# PIIzza_TIme_updated.net
KiCad netlist of a schematic drawn in EAGLE
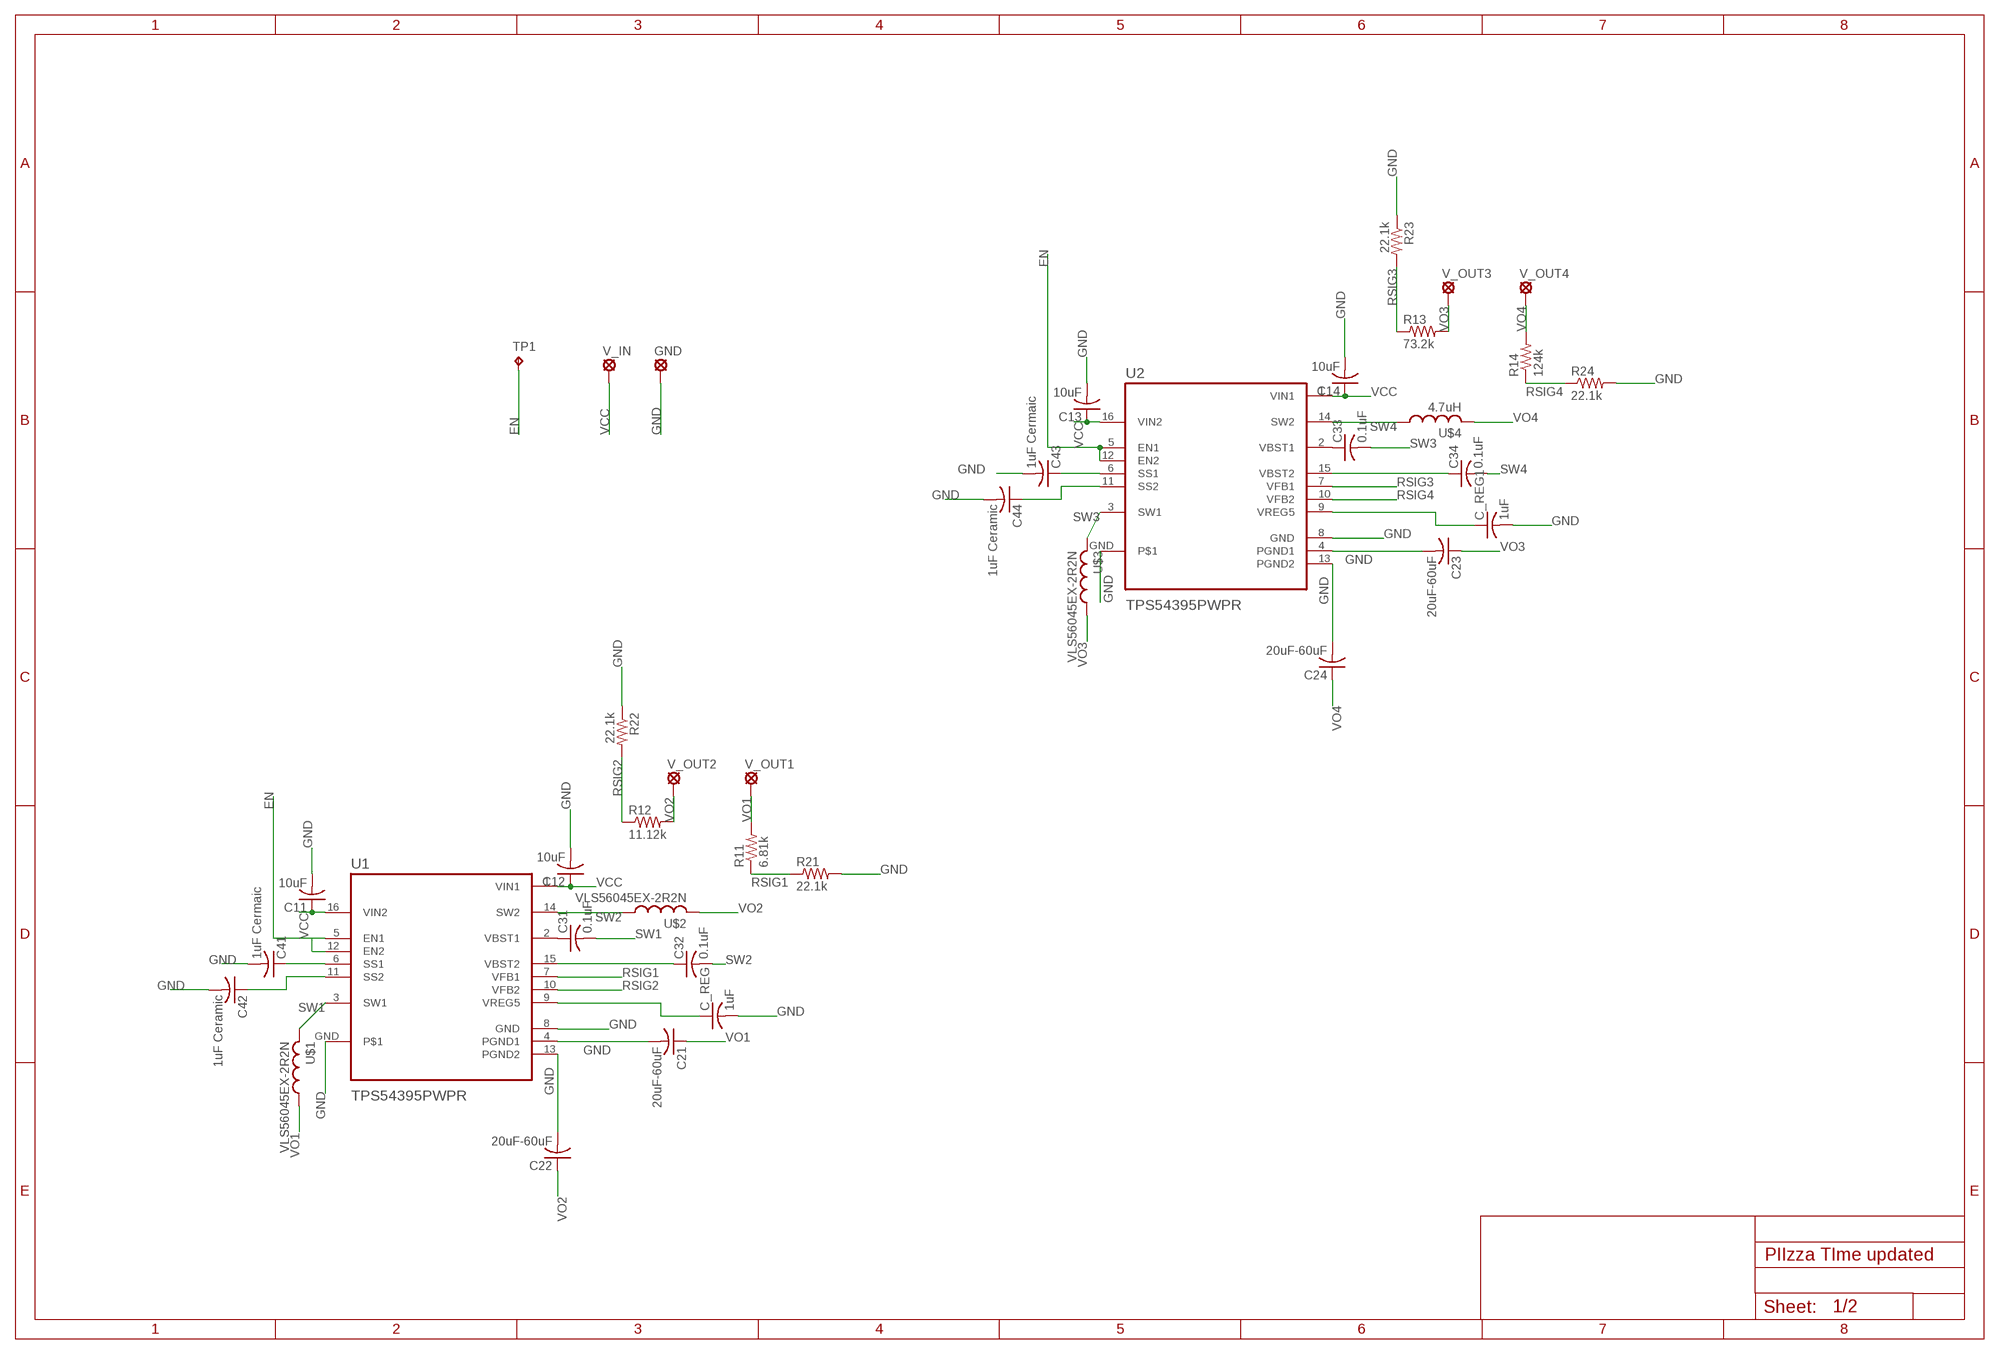
[diagram p0: schematic, sheet 1]
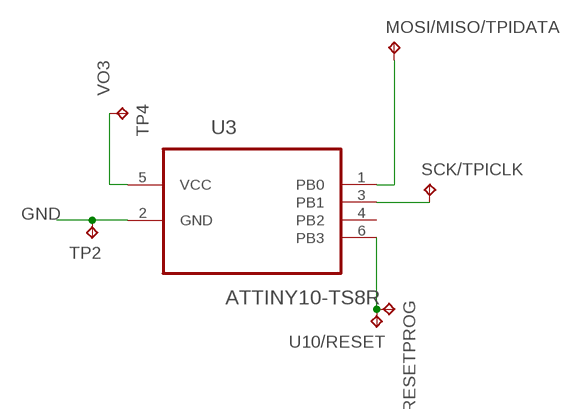
[diagram p1: schematic, sheet 2]

(export (version "E")
  (design (tool "Eeschema 10.0.6"))
  (components
    (comp (ref "MOSI/MISO/TPIDATA")
      (value "TPB2,54")
      (footprint "eagle-import:B2,54")
      (libsource (lib "eagle-import") (part "TPB2,54"))
    )
    (comp (ref "RESETPROG")
      (value "TPB2,54")
      (footprint "eagle-import:B2,54")
      (libsource (lib "eagle-import") (part "TPB2,54"))
    )
    (comp (ref "SCK/TPICLK")
      (value "TPB2,54")
      (footprint "eagle-import:B2,54")
      (libsource (lib "eagle-import") (part "TPB2,54"))
    )
    (comp (ref "TP2")
      (value "TPB2,54")
      (footprint "eagle-import:B2,54")
      (libsource (lib "eagle-import") (part "TPB2,54"))
    )
    (comp (ref "TP4")
      (value "TPB2,54")
      (footprint "eagle-import:B2,54")
      (libsource (lib "eagle-import") (part "TPB2,54"))
    )
    (comp (ref "U3")
      (value "ATTINY10-TS8R")
      (footprint "eagle-import:SOT95P280X145-6N")
      (fields (field (name "MF") "Microchip"))
      (libsource (lib "eagle-import") (part "ATTINY10-TS8R"))
    )
    (comp (ref "U10/RESET")
      (value "TPB2,54")
      (footprint "eagle-import:B2,54")
      (libsource (lib "eagle-import") (part "TPB2,54"))
    )
    (comp (ref "C11")
      (value "10uF")
      (footprint "eagle-import:C0805")
      (libsource (lib "eagle-import") (part "C-USC0805"))
    )
    (comp (ref "C12")
      (value "10uF")
      (footprint "eagle-import:C0805")
      (libsource (lib "eagle-import") (part "C-USC0805"))
    )
    (comp (ref "C13")
      (value "10uF")
      (footprint "eagle-import:C0805")
      (libsource (lib "eagle-import") (part "C-USC0805"))
    )
    (comp (ref "C14")
      (value "10uF")
      (footprint "eagle-import:C0805")
      (libsource (lib "eagle-import") (part "C-USC0805"))
    )
    (comp (ref "C21")
      (value "20uF-60uF")
      (footprint "eagle-import:C0805")
      (libsource (lib "eagle-import") (part "C-USC0805"))
    )
    (comp (ref "C22")
      (value "20uF-60uF")
      (footprint "eagle-import:C0805")
      (libsource (lib "eagle-import") (part "C-USC0805"))
    )
    (comp (ref "C23")
      (value "20uF-60uF")
      (footprint "eagle-import:C0805")
      (libsource (lib "eagle-import") (part "C-USC0805"))
    )
    (comp (ref "C24")
      (value "20uF-60uF")
      (footprint "eagle-import:C0805")
      (libsource (lib "eagle-import") (part "C-USC0805"))
    )
    (comp (ref "C31")
      (value "0.1uF")
      (footprint "eagle-import:C0805")
      (libsource (lib "eagle-import") (part "C-USC0805"))
    )
    (comp (ref "C32")
      (value "0.1uF")
      (footprint "eagle-import:C0805")
      (libsource (lib "eagle-import") (part "C-USC0805"))
    )
    (comp (ref "C33")
      (value "0.1uF")
      (footprint "eagle-import:C0805")
      (libsource (lib "eagle-import") (part "C-USC0805"))
    )
    (comp (ref "C34")
      (value "0.1uF")
      (footprint "eagle-import:C0805")
      (libsource (lib "eagle-import") (part "C-USC0805"))
    )
    (comp (ref "C41")
      (value "1uF Cermaic")
      (footprint "eagle-import:C0805")
      (libsource (lib "eagle-import") (part "C-USC0805"))
    )
    (comp (ref "C42")
      (value "1uF Ceramic")
      (footprint "eagle-import:C0805")
      (libsource (lib "eagle-import") (part "C-USC0805"))
    )
    (comp (ref "C43")
      (value "1uF Cermaic")
      (footprint "eagle-import:C0805")
      (libsource (lib "eagle-import") (part "C-USC0805"))
    )
    (comp (ref "C44")
      (value "1uF Ceramic")
      (footprint "eagle-import:C0805")
      (libsource (lib "eagle-import") (part "C-USC0805"))
    )
    (comp (ref "C_REG")
      (value "1uF")
      (footprint "eagle-import:C0805")
      (libsource (lib "eagle-import") (part "C-USC0805"))
    )
    (comp (ref "C_REG1")
      (value "1uF")
      (footprint "eagle-import:C0805")
      (libsource (lib "eagle-import") (part "C-USC0805"))
    )
    (comp (ref "GND")
      (value "SE11")
      (footprint "eagle-import:SE11")
      (libsource (lib "eagle-import") (part "SE11"))
    )
    (comp (ref "R11")
      (value "6.81k")
      (footprint "eagle-import:M0805")
      (libsource (lib "eagle-import") (part "R-US_M0805"))
    )
    (comp (ref "R12")
      (value "11.12k")
      (footprint "eagle-import:M0805")
      (libsource (lib "eagle-import") (part "R-US_M0805"))
    )
    (comp (ref "R13")
      (value "73.2k")
      (footprint "eagle-import:M0805")
      (libsource (lib "eagle-import") (part "R-US_M0805"))
    )
    (comp (ref "R14")
      (value "124k")
      (footprint "eagle-import:M0805")
      (libsource (lib "eagle-import") (part "R-US_M0805"))
    )
    (comp (ref "R21")
      (value "22.1k")
      (footprint "eagle-import:M0805")
      (libsource (lib "eagle-import") (part "R-US_M0805"))
    )
    (comp (ref "R22")
      (value "22.1k")
      (footprint "eagle-import:M0805")
      (libsource (lib "eagle-import") (part "R-US_M0805"))
    )
    (comp (ref "R23")
      (value "22.1k")
      (footprint "eagle-import:M0805")
      (libsource (lib "eagle-import") (part "R-US_M0805"))
    )
    (comp (ref "R24")
      (value "22.1k")
      (footprint "eagle-import:M0805")
      (libsource (lib "eagle-import") (part "R-US_M0805"))
    )
    (comp (ref "TP1")
      (value "TPB1,27")
      (footprint "eagle-import:B1,27")
      (libsource (lib "eagle-import") (part "TPB1,27"))
    )
    (comp (ref "U$1")
      (value "VLS56045EX-2R2N")
      (footprint "eagle-import:VLS")
      (libsource (lib "eagle-import") (part "VLS56045EX-2R2N"))
    )
    (comp (ref "U$2")
      (value "VLS56045EX-2R2N")
      (footprint "eagle-import:VLS")
      (libsource (lib "eagle-import") (part "VLS56045EX-2R2N"))
    )
    (comp (ref "U$3")
      (value "VLS56045EX-2R2N")
      (footprint "eagle-import:VLS")
      (libsource (lib "eagle-import") (part "VLS56045EX-2R2N"))
    )
    (comp (ref "U$4")
      (value "4.7uH")
      (footprint "eagle-import:VLS")
      (libsource (lib "eagle-import") (part "VLS56045EX-2R2N"))
    )
    (comp (ref "U1")
      (value "TPS54395PWPR")
      (footprint "eagle-import:SOP65P640X120-17N")
      (fields (field (name "MF") "Texas Instruments"))
      (libsource (lib "eagle-import") (part "TPS54395PWPR"))
    )
    (comp (ref "U2")
      (value "TPS54395PWPR")
      (footprint "eagle-import:SOP65P640X120-17N")
      (fields (field (name "MF") "Texas Instruments"))
      (libsource (lib "eagle-import") (part "TPS54395PWPR"))
    )
    (comp (ref "V_IN")
      (value "LSP11")
      (footprint "eagle-import:LSP11")
      (libsource (lib "eagle-import") (part "LSP11"))
    )
    (comp (ref "V_OUT1")
      (value "LSP11")
      (footprint "eagle-import:LSP11")
      (libsource (lib "eagle-import") (part "LSP11"))
    )
    (comp (ref "V_OUT2")
      (value "LSP11")
      (footprint "eagle-import:LSP11")
      (libsource (lib "eagle-import") (part "LSP11"))
    )
    (comp (ref "V_OUT3")
      (value "LSP11")
      (footprint "eagle-import:LSP11")
      (libsource (lib "eagle-import") (part "LSP11"))
    )
    (comp (ref "V_OUT4")
      (value "LSP11")
      (footprint "eagle-import:LSP11")
      (libsource (lib "eagle-import") (part "LSP11"))
    )
  )
  (nets
    (net (code "1") (name "EN") (class "Default")
      (node (ref "TP1") (pin "TP") (pinfunction "TP_TP") (pintype "input"))
      (node (ref "U1") (pin "12") (pinfunction "EN2_12") (pintype "bidirectional"))
      (node (ref "U1") (pin "5") (pinfunction "EN1_5") (pintype "bidirectional"))
      (node (ref "U2") (pin "12") (pinfunction "EN2_12") (pintype "bidirectional"))
      (node (ref "U2") (pin "5") (pinfunction "EN1_5") (pintype "bidirectional"))
    )
    (net (code "2") (name "GND") (class "Default")
      (node (ref "C11") (pin "2") (pinfunction "2_2") (pintype "passive"))
      (node (ref "C12") (pin "2") (pinfunction "2_2") (pintype "passive"))
      (node (ref "C13") (pin "2") (pinfunction "2_2") (pintype "passive"))
      (node (ref "C14") (pin "2") (pinfunction "2_2") (pintype "passive"))
      (node (ref "C21") (pin "2") (pinfunction "2_2") (pintype "passive"))
      (node (ref "C22") (pin "2") (pinfunction "2_2") (pintype "passive"))
      (node (ref "C23") (pin "2") (pinfunction "2_2") (pintype "passive"))
      (node (ref "C24") (pin "2") (pinfunction "2_2") (pintype "passive"))
      (node (ref "C41") (pin "2") (pinfunction "2_2") (pintype "passive"))
      (node (ref "C42") (pin "2") (pinfunction "2_2") (pintype "passive"))
      (node (ref "C43") (pin "2") (pinfunction "2_2") (pintype "passive"))
      (node (ref "C44") (pin "2") (pinfunction "2_2") (pintype "passive"))
      (node (ref "C_REG") (pin "2") (pinfunction "2_2") (pintype "passive"))
      (node (ref "C_REG1") (pin "2") (pinfunction "2_2") (pintype "passive"))
      (node (ref "GND") (pin "MP") (pinfunction "MP_MP") (pintype "passive"))
      (node (ref "R21") (pin "2") (pinfunction "2_2") (pintype "passive"))
      (node (ref "R22") (pin "1") (pinfunction "1_1") (pintype "passive"))
      (node (ref "R23") (pin "1") (pinfunction "1_1") (pintype "passive"))
      (node (ref "R24") (pin "2") (pinfunction "2_2") (pintype "passive"))
      (node (ref "TP2") (pin "TP") (pinfunction "TP_TP") (pintype "input"))
      (node (ref "U1") (pin "13") (pinfunction "PGND2_13") (pintype "power_in"))
      (node (ref "U1") (pin "4") (pinfunction "PGND1_4") (pintype "power_in"))
      (node (ref "U1") (pin "8") (pinfunction "GND_8") (pintype "power_in"))
      (node (ref "U1") (pin "GND") (pinfunction "P$1_GND") (pintype "bidirectional"))
      (node (ref "U2") (pin "13") (pinfunction "PGND2_13") (pintype "power_in"))
      (node (ref "U2") (pin "4") (pinfunction "PGND1_4") (pintype "power_in"))
      (node (ref "U2") (pin "8") (pinfunction "GND_8") (pintype "power_in"))
      (node (ref "U2") (pin "GND") (pinfunction "P$1_GND") (pintype "bidirectional"))
      (node (ref "U3") (pin "2") (pinfunction "GND_2") (pintype "passive"))
    )
    (net (code "3") (name "Net-(U1-SS1)") (class "Default")
      (node (ref "C41") (pin "1") (pinfunction "1_1") (pintype "passive"))
      (node (ref "U1") (pin "6") (pinfunction "SS1_6") (pintype "bidirectional"))
    )
    (net (code "4") (name "Net-(U1-SS2)") (class "Default")
      (node (ref "C42") (pin "1") (pinfunction "1_1") (pintype "passive"))
      (node (ref "U1") (pin "11") (pinfunction "SS2_11") (pintype "bidirectional"))
    )
    (net (code "5") (name "Net-(U1-VBST1)") (class "Default")
      (node (ref "C31") (pin "1") (pinfunction "1_1") (pintype "passive"))
      (node (ref "U1") (pin "2") (pinfunction "VBST1_2") (pintype "bidirectional"))
    )
    (net (code "6") (name "Net-(U1-VBST2)") (class "Default")
      (node (ref "C32") (pin "1") (pinfunction "1_1") (pintype "passive"))
      (node (ref "U1") (pin "15") (pinfunction "VBST2_15") (pintype "bidirectional"))
    )
    (net (code "7") (name "Net-(U1-VREG5)") (class "Default")
      (node (ref "C_REG") (pin "1") (pinfunction "1_1") (pintype "passive"))
      (node (ref "U1") (pin "9") (pinfunction "VREG5_9") (pintype "bidirectional"))
    )
    (net (code "8") (name "Net-(U2-SS1)") (class "Default")
      (node (ref "C43") (pin "1") (pinfunction "1_1") (pintype "passive"))
      (node (ref "U2") (pin "6") (pinfunction "SS1_6") (pintype "bidirectional"))
    )
    (net (code "9") (name "Net-(U2-SS2)") (class "Default")
      (node (ref "C44") (pin "1") (pinfunction "1_1") (pintype "passive"))
      (node (ref "U2") (pin "11") (pinfunction "SS2_11") (pintype "bidirectional"))
    )
    (net (code "10") (name "Net-(U2-VBST1)") (class "Default")
      (node (ref "C33") (pin "1") (pinfunction "1_1") (pintype "passive"))
      (node (ref "U2") (pin "2") (pinfunction "VBST1_2") (pintype "bidirectional"))
    )
    (net (code "11") (name "Net-(U2-VBST2)") (class "Default")
      (node (ref "C34") (pin "1") (pinfunction "1_1") (pintype "passive"))
      (node (ref "U2") (pin "15") (pinfunction "VBST2_15") (pintype "bidirectional"))
    )
    (net (code "12") (name "Net-(U2-VREG5)") (class "Default")
      (node (ref "C_REG1") (pin "1") (pinfunction "1_1") (pintype "passive"))
      (node (ref "U2") (pin "9") (pinfunction "VREG5_9") (pintype "bidirectional"))
    )
    (net (code "13") (name "Net-(U3-PB0)") (class "Default")
      (node (ref "MOSI/MISO/TPIDATA") (pin "TP") (pinfunction "TP_TP") (pintype "input"))
      (node (ref "U3") (pin "1") (pinfunction "PB0_1") (pintype "bidirectional"))
    )
    (net (code "14") (name "Net-(U3-PB1)") (class "Default")
      (node (ref "SCK/TPICLK") (pin "TP") (pinfunction "TP_TP") (pintype "input"))
      (node (ref "U3") (pin "3") (pinfunction "PB1_3") (pintype "bidirectional"))
    )
    (net (code "15") (name "Net-(U3-PB3)") (class "Default")
      (node (ref "RESETPROG") (pin "TP") (pinfunction "TP_TP") (pintype "input"))
      (node (ref "U10/RESET") (pin "TP") (pinfunction "TP_TP") (pintype "input"))
      (node (ref "U3") (pin "6") (pinfunction "PB3_6") (pintype "bidirectional"))
    )
    (net (code "16") (name "RSIG1") (class "Default")
      (node (ref "R11") (pin "1") (pinfunction "1_1") (pintype "passive"))
      (node (ref "R21") (pin "1") (pinfunction "1_1") (pintype "passive"))
      (node (ref "U1") (pin "7") (pinfunction "VFB1_7") (pintype "bidirectional"))
    )
    (net (code "17") (name "RSIG2") (class "Default")
      (node (ref "R12") (pin "1") (pinfunction "1_1") (pintype "passive"))
      (node (ref "R22") (pin "2") (pinfunction "2_2") (pintype "passive"))
      (node (ref "U1") (pin "10") (pinfunction "VFB2_10") (pintype "bidirectional"))
    )
    (net (code "18") (name "RSIG3") (class "Default")
      (node (ref "R13") (pin "1") (pinfunction "1_1") (pintype "passive"))
      (node (ref "R23") (pin "2") (pinfunction "2_2") (pintype "passive"))
      (node (ref "U2") (pin "7") (pinfunction "VFB1_7") (pintype "bidirectional"))
    )
    (net (code "19") (name "RSIG4") (class "Default")
      (node (ref "R14") (pin "1") (pinfunction "1_1") (pintype "passive"))
      (node (ref "R24") (pin "1") (pinfunction "1_1") (pintype "passive"))
      (node (ref "U2") (pin "10") (pinfunction "VFB2_10") (pintype "bidirectional"))
    )
    (net (code "20") (name "SW1") (class "Default")
      (node (ref "C31") (pin "2") (pinfunction "2_2") (pintype "passive"))
      (node (ref "U$1") (pin "P$2") (pinfunction "2_P$2") (pintype "passive"))
      (node (ref "U1") (pin "3") (pinfunction "SW1_3") (pintype "bidirectional"))
    )
    (net (code "21") (name "SW2") (class "Default")
      (node (ref "C32") (pin "2") (pinfunction "2_2") (pintype "passive"))
      (node (ref "U$2") (pin "P$1") (pinfunction "1_P$1") (pintype "passive"))
      (node (ref "U1") (pin "14") (pinfunction "SW2_14") (pintype "bidirectional"))
    )
    (net (code "22") (name "SW3") (class "Default")
      (node (ref "C33") (pin "2") (pinfunction "2_2") (pintype "passive"))
      (node (ref "U$3") (pin "P$2") (pinfunction "2_P$2") (pintype "passive"))
      (node (ref "U2") (pin "3") (pinfunction "SW1_3") (pintype "bidirectional"))
    )
    (net (code "23") (name "SW4") (class "Default")
      (node (ref "C34") (pin "2") (pinfunction "2_2") (pintype "passive"))
      (node (ref "U$4") (pin "P$1") (pinfunction "1_P$1") (pintype "passive"))
      (node (ref "U2") (pin "14") (pinfunction "SW2_14") (pintype "bidirectional"))
    )
    (net (code "24") (name "VCC") (class "Default")
      (node (ref "C11") (pin "1") (pinfunction "1_1") (pintype "passive"))
      (node (ref "C12") (pin "1") (pinfunction "1_1") (pintype "passive"))
      (node (ref "C13") (pin "1") (pinfunction "1_1") (pintype "passive"))
      (node (ref "C14") (pin "1") (pinfunction "1_1") (pintype "passive"))
      (node (ref "U1") (pin "1") (pinfunction "VIN1_1") (pintype "power_in"))
      (node (ref "U1") (pin "16") (pinfunction "VIN2_16") (pintype "input"))
      (node (ref "U2") (pin "1") (pinfunction "VIN1_1") (pintype "power_in"))
      (node (ref "U2") (pin "16") (pinfunction "VIN2_16") (pintype "input"))
      (node (ref "V_IN") (pin "MP") (pinfunction "MP_MP") (pintype "passive"))
    )
    (net (code "25") (name "VO1") (class "Default")
      (node (ref "C21") (pin "1") (pinfunction "1_1") (pintype "passive"))
      (node (ref "R11") (pin "2") (pinfunction "2_2") (pintype "passive"))
      (node (ref "U$1") (pin "P$1") (pinfunction "1_P$1") (pintype "passive"))
      (node (ref "V_OUT1") (pin "MP") (pinfunction "MP_MP") (pintype "passive"))
    )
    (net (code "26") (name "VO2") (class "Default")
      (node (ref "C22") (pin "1") (pinfunction "1_1") (pintype "passive"))
      (node (ref "R12") (pin "2") (pinfunction "2_2") (pintype "passive"))
      (node (ref "U$2") (pin "P$2") (pinfunction "2_P$2") (pintype "passive"))
      (node (ref "V_OUT2") (pin "MP") (pinfunction "MP_MP") (pintype "passive"))
    )
    (net (code "27") (name "VO3") (class "Default")
      (node (ref "C23") (pin "1") (pinfunction "1_1") (pintype "passive"))
      (node (ref "R13") (pin "2") (pinfunction "2_2") (pintype "passive"))
      (node (ref "TP4") (pin "TP") (pinfunction "TP_TP") (pintype "input"))
      (node (ref "U$3") (pin "P$1") (pinfunction "1_P$1") (pintype "passive"))
      (node (ref "U3") (pin "5") (pinfunction "VCC_5") (pintype "power_in"))
      (node (ref "V_OUT3") (pin "MP") (pinfunction "MP_MP") (pintype "passive"))
    )
    (net (code "28") (name "VO4") (class "Default")
      (node (ref "C24") (pin "1") (pinfunction "1_1") (pintype "passive"))
      (node (ref "R14") (pin "2") (pinfunction "2_2") (pintype "passive"))
      (node (ref "U$4") (pin "P$2") (pinfunction "2_P$2") (pintype "passive"))
      (node (ref "V_OUT4") (pin "MP") (pinfunction "MP_MP") (pintype "passive"))
    )
    (net (code "29") (name "unconnected-(U3-PB2-Pad4)") (class "Default")
      (node (ref "U3") (pin "4") (pinfunction "PB2_4") (pintype "bidirectional"))
    )
  )
)
